# ProProject_007aLS_2024-05-12.net
KiCad netlist of a schematic drawn in EasyEDA Pro
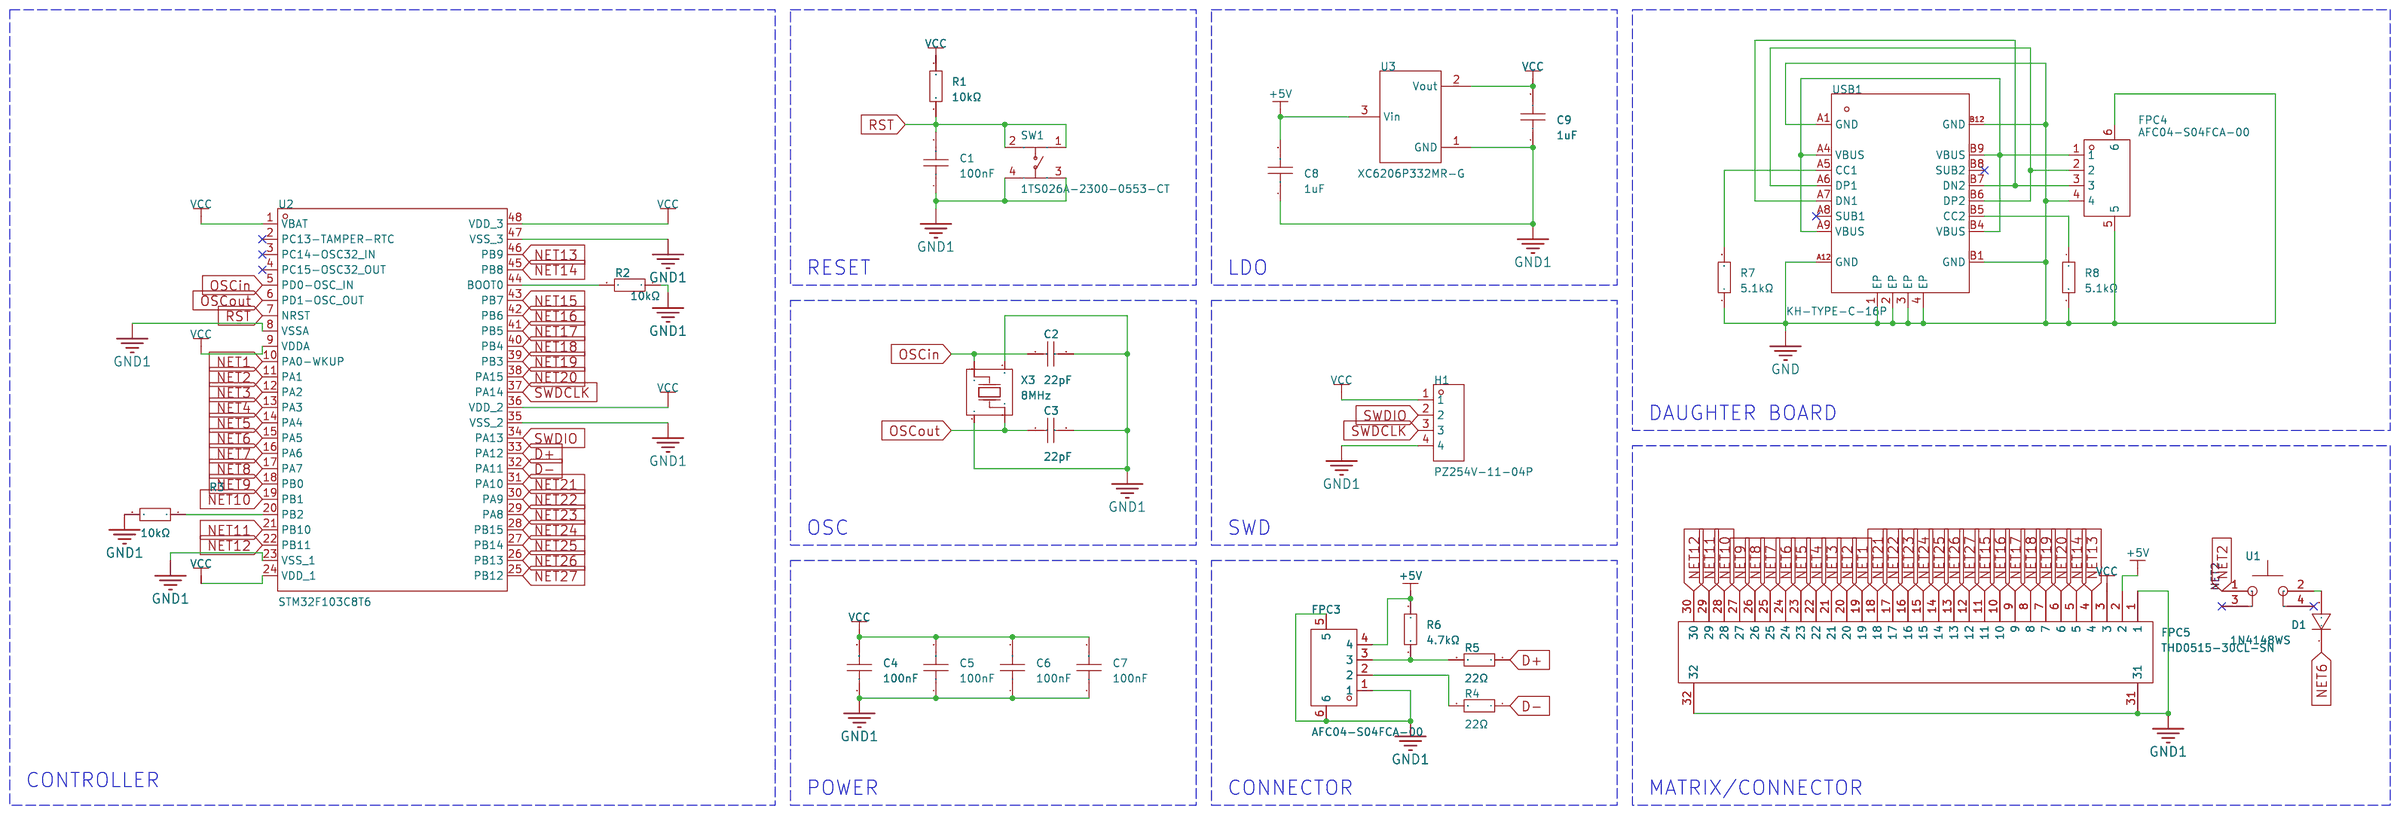
[diagram p0: schematic sheet]

(export (version "E")
  (design (tool "Eeschema 10.0.6"))
  (components
    (comp (ref "C1")
      (value "100nF")
      (footprint "easyedapro:C0603")
      (description "容值:100nF;精度:±10%;额定电压:50V;材质(温度系数):X7R;")
      (fields
        (field (name "Manufacturer Part") "CC0603KRX7R9BB104")
        (field (name "Manufacturer") "YAGEO(国巨)")
      )
      (libsource (lib "easyedapro") (part "CC0603KRX7R9BB104"))
    )
    (comp (ref "C2")
      (value "22pF")
      (footprint "easyedapro:C0603")
      (description "容值:22pF;精度:±5%;额定电压:50V;材质(温度系数):C0G;")
      (fields
        (field (name "Manufacturer Part") "CL10C220JB8NNNC")
        (field (name "Manufacturer") "SAMSUNG(三星)")
      )
      (libsource (lib "easyedapro") (part "CL10C220JB8NNNC"))
    )
    (comp (ref "C3")
      (value "22pF")
      (footprint "easyedapro:C0603")
      (description "容值:22pF;精度:±5%;额定电压:50V;材质(温度系数):C0G;")
      (fields
        (field (name "Manufacturer Part") "CL10C220JB8NNNC")
        (field (name "Manufacturer") "SAMSUNG(三星)")
      )
      (libsource (lib "easyedapro") (part "CL10C220JB8NNNC"))
    )
    (comp (ref "C4")
      (value "100nF")
      (footprint "easyedapro:C0603")
      (description "容值:100nF;精度:±10%;额定电压:50V;材质(温度系数):X7R;")
      (fields
        (field (name "Manufacturer Part") "CC0603KRX7R9BB104")
        (field (name "Manufacturer") "YAGEO(国巨)")
      )
      (libsource (lib "easyedapro") (part "CC0603KRX7R9BB104"))
    )
    (comp (ref "C5")
      (value "100nF")
      (footprint "easyedapro:C0603")
      (description "容值:100nF;精度:±10%;额定电压:50V;材质(温度系数):X7R;")
      (fields
        (field (name "Manufacturer Part") "CC0603KRX7R9BB104")
        (field (name "Manufacturer") "YAGEO(国巨)")
      )
      (libsource (lib "easyedapro") (part "CC0603KRX7R9BB104"))
    )
    (comp (ref "C6")
      (value "100nF")
      (footprint "easyedapro:C0603")
      (description "容值:100nF;精度:±10%;额定电压:50V;材质(温度系数):X7R;")
      (fields
        (field (name "Manufacturer Part") "CC0603KRX7R9BB104")
        (field (name "Manufacturer") "YAGEO(国巨)")
      )
      (libsource (lib "easyedapro") (part "CC0603KRX7R9BB104"))
    )
    (comp (ref "C7")
      (value "100nF")
      (footprint "easyedapro:C0603")
      (description "容值:100nF;精度:±10%;额定电压:50V;材质(温度系数):X7R;")
      (fields
        (field (name "Manufacturer Part") "CC0603KRX7R9BB104")
        (field (name "Manufacturer") "YAGEO(国巨)")
      )
      (libsource (lib "easyedapro") (part "CC0603KRX7R9BB104"))
    )
    (comp (ref "C8")
      (value "1uF")
      (footprint "easyedapro:C0603")
      (description "容值:1uF;精度:±10%;额定电压:50V;材质(温度系数):X5R;")
      (fields
        (field (name "Manufacturer Part") "CL10A105KB8NNNC")
        (field (name "Manufacturer") "SAMSUNG(三星)")
      )
      (libsource (lib "easyedapro") (part "CL10A105KB8NNNC"))
    )
    (comp (ref "C9")
      (value "1uF")
      (footprint "easyedapro:C0603")
      (description "容值:1uF;精度:±10%;额定电压:50V;材质(温度系数):X5R;")
      (fields
        (field (name "Manufacturer Part") "CL10A105KB8NNNC")
        (field (name "Manufacturer") "SAMSUNG(三星)")
      )
      (libsource (lib "easyedapro") (part "CL10A105KB8NNNC"))
    )
    (comp (ref "D1")
      (value "1N4148WS")
      (footprint "easyedapro:SOD-323_L1.8-W1.3-LS2.5-RD")
      (description "二极管配置:独立式;正向压降(Vf):1.25V@150mA;直流反向耐压(Vr):100V;平均整流电流(Io):150mA;功率:200mW;反向恢复时间(trr):4ns;")
      (fields (field (name "Manufacturer") "CJ(江苏长电/长晶)"))
      (libsource (lib "easyedapro") (part "1N4148WS T4"))
    )
    (comp (ref "FPC3")
      (value "AFC04-S04FCA-00")
      (footprint "easyedapro:FPC-SMD_AFC04-S04FCA-00")
      (description "锁定特性:抽屉式;触点类型:下接;触点数量:4P;间距:0.5mm;安装类型:卧贴;工作温度范围:-25°C~+85°C;")
      (fields (field (name "Manufacturer") "JS(钜硕电子)"))
      (libsource (lib "easyedapro") (part "AFC04-S04FCA-00"))
    )
    (comp (ref "FPC4")
      (value "AFC04-S04FCA-00")
      (footprint "easyedapro:FPC-SMD_AFC04-S04FCA-00")
      (description "锁定特性:抽屉式;触点类型:下接;触点数量:4P;间距:0.5mm;安装类型:卧贴;工作温度范围:-25°C~+85°C;")
      (fields (field (name "Manufacturer") "JS(钜硕电子)"))
      (libsource (lib "easyedapro") (part "AFC04-S04FCA-00"))
    )
    (comp (ref "FPC5")
      (value "THD0515-30CL-SN")
      (footprint "easyedapro:FFC-SMD_30P-P0.50_THD0515-30CL-SN")
      (description "锁定特性:翻盖式;触点类型:下接;触点数量:30P;间距:0.5mm;安装类型:卧贴;")
      (fields (field (name "Manufacturer") "THD(台华达)"))
      (libsource (lib "easyedapro") (part "THD0515-30CL-SN"))
    )
    (comp (ref "H1")
      (value "PZ254V-11-04P")
      (footprint "easyedapro:HDR-TH_4P-P2.54-V-M")
      (fields (field (name "Manufacturer") "XFCN(兴飞)"))
      (libsource (lib "easyedapro") (part "PZ254V-11-04P_C2691448"))
    )
    (comp (ref "R1")
      (value "10kΩ")
      (footprint "easyedapro:R0603")
      (description "电阻类型:厚膜电阻;阻值:10kΩ;精度:±1%;功率:100mW;最大工作电压:75V;温度系数:±100ppm/°C;")
      (fields
        (field (name "Manufacturer Part") "0603WAF1002T5E")
        (field (name "Manufacturer") "UNI-ROYAL(厚声)")
      )
      (libsource (lib "easyedapro") (part "0603WAF1002T5E"))
    )
    (comp (ref "R2")
      (value "10kΩ")
      (footprint "easyedapro:R0603")
      (description "电阻类型:厚膜电阻;阻值:10kΩ;精度:±1%;功率:100mW;最大工作电压:75V;温度系数:±100ppm/°C;")
      (fields
        (field (name "Manufacturer Part") "0603WAF1002T5E")
        (field (name "Manufacturer") "UNI-ROYAL(厚声)")
      )
      (libsource (lib "easyedapro") (part "0603WAF1002T5E"))
    )
    (comp (ref "R3")
      (value "10kΩ")
      (footprint "easyedapro:R0603")
      (description "电阻类型:厚膜电阻;阻值:10kΩ;精度:±1%;功率:100mW;最大工作电压:75V;温度系数:±100ppm/°C;")
      (fields
        (field (name "Manufacturer Part") "0603WAF1002T5E")
        (field (name "Manufacturer") "UNI-ROYAL(厚声)")
      )
      (libsource (lib "easyedapro") (part "0603WAF1002T5E"))
    )
    (comp (ref "R4")
      (value "22Ω")
      (footprint "easyedapro:R0603")
      (description "电阻类型:厚膜电阻;阻值:22Ω;精度:±1%;功率:100mW;最大工作电压:75V;温度系数:±100ppm/°C;")
      (fields
        (field (name "Manufacturer Part") "0603WAF220JT5E")
        (field (name "Manufacturer") "UNI-ROYAL(厚声)")
      )
      (libsource (lib "easyedapro") (part "0603WAF220JT5E"))
    )
    (comp (ref "R5")
      (value "22Ω")
      (footprint "easyedapro:R0603")
      (description "电阻类型:厚膜电阻;阻值:22Ω;精度:±1%;功率:100mW;最大工作电压:75V;温度系数:±100ppm/°C;")
      (fields
        (field (name "Manufacturer Part") "0603WAF220JT5E")
        (field (name "Manufacturer") "UNI-ROYAL(厚声)")
      )
      (libsource (lib "easyedapro") (part "0603WAF220JT5E"))
    )
    (comp (ref "R6")
      (value "4.7kΩ")
      (footprint "easyedapro:R0603")
      (description "电阻类型:厚膜电阻;阻值:4.7kΩ;精度:±1%;功率:100mW;最大工作电压:75V;温度系数:±100ppm/°C;")
      (fields
        (field (name "Manufacturer Part") "0603WAF4701T5E")
        (field (name "Manufacturer") "UNI-ROYAL(厚声)")
      )
      (libsource (lib "easyedapro") (part "0603WAF4701T5E"))
    )
    (comp (ref "R7")
      (value "5.1kΩ")
      (footprint "easyedapro:R0603")
      (description "电阻类型:厚膜电阻;阻值:5.1kΩ;精度:±1%;功率:100mW;最大工作电压:75V;温度系数:±100ppm/°C;")
      (fields
        (field (name "Manufacturer Part") "0603WAF5101T5E")
        (field (name "Manufacturer") "UNI-ROYAL(厚声)")
      )
      (libsource (lib "easyedapro") (part "0603WAF5101T5E"))
    )
    (comp (ref "R8")
      (value "5.1kΩ")
      (footprint "easyedapro:R0603")
      (description "电阻类型:厚膜电阻;阻值:5.1kΩ;精度:±1%;功率:100mW;最大工作电压:75V;温度系数:±100ppm/°C;")
      (fields
        (field (name "Manufacturer Part") "0603WAF5101T5E")
        (field (name "Manufacturer") "UNI-ROYAL(厚声)")
      )
      (libsource (lib "easyedapro") (part "0603WAF5101T5E"))
    )
    (comp (ref "SW1")
      (value "1TS026A-2300-0553-CT")
      (footprint "easyedapro:SW-SMD_4P-L2.6-W1.6-P0.75-LS3.0")
      (fields (field (name "Manufacturer") "HYP(鸿源精密)"))
      (libsource (lib "easyedapro") (part "1TS026A-2300-0553-CT"))
    )
    (comp (ref "U1")
      (value "~")
      (footprint "easyedapro:MXOnly-6.25U/7U-Hotswap-ReversedStabilizers")
      (libsource (lib "easyedapro") (part "MXOnly-6.25U/7U-Hotswap-ReversedStabilizers"))
    )
    (comp (ref "U2")
      (value "STM32F103C8T6")
      (footprint "easyedapro:LQFP-48_L7.0-W7.0-P0.50-LS9.0-BL")
      (description "CPU内核:CM3;程序存储容量:64KB;RAM总容量:20KB;GPIO端口数量:37;工作电压范围:2V~3.6V;CPU最大主频:72MHz;程序存储器类型:FLASH;")
      (fields (field (name "Manufacturer") "ST(意法半导体)"))
      (libsource (lib "easyedapro") (part "STM32F103C8T6"))
    )
    (comp (ref "U3")
      (value "XC6206P332MR-G")
      (footprint "easyedapro:SOT-23-3_L2.9-W1.6-P1.90-LS2.8-BR")
      (description "输出类型:固定;最大输入电压:6V;输出电压:3.3V;最大输出电流:200mA;电源纹波抑制比(PSRR):-;输出极性:正极;")
      (fields (field (name "Manufacturer") "TOREX(特瑞仕)"))
      (libsource (lib "easyedapro") (part "XC6206P332MR"))
    )
    (comp (ref "USB1")
      (value "KH-TYPE-C-16P")
      (footprint "easyedapro:USB-C-SMD_KH-TYPE-C-16P")
      (description "连接器类型:Type-C;标准:-;公母:母;端口数量:1;触点数量:16P;安装方式:卧贴;额定电流 - 电源:3A;工作温度范围:-40°C~+85°C;")
      (fields (field (name "Manufacturer") "kinghelm(金航标)"))
      (libsource (lib "easyedapro") (part "KH-TYPE-C-16P"))
    )
    (comp (ref "X3")
      (value "8MHz")
      (footprint "easyedapro:OSC-SMD_4P-L3.2-W2.5-BL")
      (description "晶振类型:贴片晶振;频率:8MHz;常温频差:±10ppm;外接负载电容:10pF;频率稳定度(全温):±15ppm;")
      (fields (field (name "Manufacturer Part") "TAXM8M4RDBCCT2T") (field (name "Manufacturer") "YJX(雅晶鑫)"))
      (libsource (lib "easyedapro") (part "TAXM8M4RDBCCT2T"))
    )
  )
  (nets
    (net (code "1") (name "+5V") (class "Default")
      (node (ref "C8") (pin "2") (pinfunction "2_2") (pintype "unspecified"))
      (node (ref "FPC3") (pin "4") (pinfunction "4_4") (pintype "unspecified"))
      (node (ref "FPC5") (pin "2") (pinfunction "2_2") (pintype "unspecified"))
      (node (ref "R6") (pin "2") (pinfunction "2_2") (pintype "input"))
      (node (ref "U3") (pin "3") (pinfunction "Vin_3") (pintype "unspecified"))
    )
    (net (code "2") (name "D+") (class "Default")
      (node (ref "R5") (pin "1") (pinfunction "1_1") (pintype "input"))
      (node (ref "U2") (pin "33") (pinfunction "PA12_33") (pintype "unspecified"))
    )
    (net (code "3") (name "D-") (class "Default")
      (node (ref "R4") (pin "1") (pinfunction "1_1") (pintype "input"))
      (node (ref "U2") (pin "32") (pinfunction "PA11_32") (pintype "unspecified"))
    )
    (net (code "4") (name "GND") (class "Default")
      (node (ref "FPC4") (pin "4") (pinfunction "4_4") (pintype "unspecified"))
      (node (ref "FPC4") (pin "5") (pinfunction "5_5") (pintype "unspecified"))
      (node (ref "FPC4") (pin "6") (pinfunction "6_6") (pintype "unspecified"))
      (node (ref "R7") (pin "1") (pinfunction "1_1") (pintype "input"))
      (node (ref "R8") (pin "2") (pinfunction "2_2") (pintype "input"))
      (node (ref "USB1") (pin "1") (pinfunction "EP_1") (pintype "unspecified"))
      (node (ref "USB1") (pin "2") (pinfunction "EP_2") (pintype "unspecified"))
      (node (ref "USB1") (pin "3") (pinfunction "EP_3") (pintype "unspecified"))
      (node (ref "USB1") (pin "4") (pinfunction "EP_4") (pintype "unspecified"))
      (node (ref "USB1") (pin "A1") (pinfunction "GND_A1") (pintype "unspecified"))
      (node (ref "USB1") (pin "A12") (pinfunction "GND_A12") (pintype "unspecified"))
      (node (ref "USB1") (pin "B1") (pinfunction "GND_B1") (pintype "unspecified"))
      (node (ref "USB1") (pin "B12") (pinfunction "GND_B12") (pintype "unspecified"))
    )
    (net (code "5") (name "GND1") (class "Default")
      (node (ref "C1") (pin "1") (pinfunction "1_1") (pintype "unspecified"))
      (node (ref "C2") (pin "2") (pinfunction "2_2") (pintype "input"))
      (node (ref "C3") (pin "2") (pinfunction "2_2") (pintype "input"))
      (node (ref "C4") (pin "1") (pinfunction "1_1") (pintype "unspecified"))
      (node (ref "C5") (pin "1") (pinfunction "1_1") (pintype "unspecified"))
      (node (ref "C6") (pin "1") (pinfunction "1_1") (pintype "unspecified"))
      (node (ref "C7") (pin "1") (pinfunction "1_1") (pintype "unspecified"))
      (node (ref "C8") (pin "1") (pinfunction "1_1") (pintype "unspecified"))
      (node (ref "C9") (pin "1") (pinfunction "1_1") (pintype "unspecified"))
      (node (ref "FPC3") (pin "1") (pinfunction "1_1") (pintype "unspecified"))
      (node (ref "FPC3") (pin "5") (pinfunction "5_5") (pintype "unspecified"))
      (node (ref "FPC3") (pin "6") (pinfunction "6_6") (pintype "unspecified"))
      (node (ref "FPC5") (pin "1") (pinfunction "1_1") (pintype "unspecified"))
      (node (ref "FPC5") (pin "31") (pinfunction "31_31") (pintype "unspecified"))
      (node (ref "FPC5") (pin "32") (pinfunction "32_32") (pintype "unspecified"))
      (node (ref "H1") (pin "4") (pinfunction "4_4") (pintype "unspecified"))
      (node (ref "R2") (pin "1") (pinfunction "1_1") (pintype "input"))
      (node (ref "R3") (pin "2") (pinfunction "2_2") (pintype "input"))
      (node (ref "SW1") (pin "3") (pinfunction "3_3") (pintype "input"))
      (node (ref "SW1") (pin "4") (pinfunction "4_4") (pintype "input"))
      (node (ref "U2") (pin "23") (pinfunction "VSS_1_23") (pintype "unspecified"))
      (node (ref "U2") (pin "35") (pinfunction "VSS_2_35") (pintype "unspecified"))
      (node (ref "U2") (pin "47") (pinfunction "VSS_3_47") (pintype "unspecified"))
      (node (ref "U2") (pin "8") (pinfunction "VSSA_8") (pintype "unspecified"))
      (node (ref "U3") (pin "1") (pinfunction "GND_1") (pintype "unspecified"))
      (node (ref "X3") (pin "2") (pinfunction "2_2") (pintype "input"))
      (node (ref "X3") (pin "4") (pinfunction "4_4") (pintype "input"))
    )
    (net (code "6") (name "NET1") (class "Default")
      (node (ref "FPC5") (pin "19") (pinfunction "19_19") (pintype "unspecified"))
      (node (ref "U2") (pin "10") (pinfunction "PA0-WKUP_10") (pintype "unspecified"))
    )
    (net (code "7") (name "NET2") (class "Default")
      (node (ref "FPC5") (pin "20") (pinfunction "20_20") (pintype "unspecified"))
      (node (ref "U1") (pin "1") (pinfunction "1_1") (pintype "input"))
      (node (ref "U2") (pin "11") (pinfunction "PA1_11") (pintype "unspecified"))
    )
    (net (code "8") (name "NET3") (class "Default")
      (node (ref "FPC5") (pin "21") (pinfunction "21_21") (pintype "unspecified"))
      (node (ref "U2") (pin "12") (pinfunction "PA2_12") (pintype "unspecified"))
    )
    (net (code "9") (name "NET4") (class "Default")
      (node (ref "FPC5") (pin "22") (pinfunction "22_22") (pintype "unspecified"))
      (node (ref "U2") (pin "13") (pinfunction "PA3_13") (pintype "unspecified"))
    )
    (net (code "10") (name "NET5") (class "Default")
      (node (ref "FPC5") (pin "23") (pinfunction "23_23") (pintype "unspecified"))
      (node (ref "U2") (pin "14") (pinfunction "PA4_14") (pintype "unspecified"))
    )
    (net (code "11") (name "NET6") (class "Default")
      (node (ref "D1") (pin "1") (pinfunction "K_1") (pintype "unspecified"))
      (node (ref "FPC5") (pin "24") (pinfunction "24_24") (pintype "unspecified"))
      (node (ref "U2") (pin "15") (pinfunction "PA5_15") (pintype "unspecified"))
    )
    (net (code "12") (name "NET7") (class "Default")
      (node (ref "FPC5") (pin "25") (pinfunction "25_25") (pintype "unspecified"))
      (node (ref "U2") (pin "16") (pinfunction "PA6_16") (pintype "unspecified"))
    )
    (net (code "13") (name "NET8") (class "Default")
      (node (ref "FPC5") (pin "26") (pinfunction "26_26") (pintype "unspecified"))
      (node (ref "U2") (pin "17") (pinfunction "PA7_17") (pintype "unspecified"))
    )
    (net (code "14") (name "NET9") (class "Default")
      (node (ref "FPC5") (pin "27") (pinfunction "27_27") (pintype "unspecified"))
      (node (ref "U2") (pin "18") (pinfunction "PB0_18") (pintype "unspecified"))
    )
    (net (code "15") (name "NET10") (class "Default")
      (node (ref "FPC5") (pin "28") (pinfunction "28_28") (pintype "unspecified"))
      (node (ref "U2") (pin "19") (pinfunction "PB1_19") (pintype "unspecified"))
    )
    (net (code "16") (name "NET11") (class "Default")
      (node (ref "FPC5") (pin "29") (pinfunction "29_29") (pintype "unspecified"))
      (node (ref "U2") (pin "21") (pinfunction "PB10_21") (pintype "unspecified"))
    )
    (net (code "17") (name "NET12") (class "Default")
      (node (ref "FPC5") (pin "30") (pinfunction "30_30") (pintype "unspecified"))
      (node (ref "U2") (pin "22") (pinfunction "PB11_22") (pintype "unspecified"))
    )
    (net (code "18") (name "NET13") (class "Default")
      (node (ref "FPC5") (pin "4") (pinfunction "4_4") (pintype "unspecified"))
      (node (ref "U2") (pin "46") (pinfunction "PB9_46") (pintype "unspecified"))
    )
    (net (code "19") (name "NET14") (class "Default")
      (node (ref "FPC5") (pin "5") (pinfunction "5_5") (pintype "unspecified"))
      (node (ref "U2") (pin "45") (pinfunction "PB8_45") (pintype "unspecified"))
    )
    (net (code "20") (name "NET15") (class "Default")
      (node (ref "FPC5") (pin "11") (pinfunction "11_11") (pintype "unspecified"))
      (node (ref "U2") (pin "43") (pinfunction "PB7_43") (pintype "unspecified"))
    )
    (net (code "21") (name "NET16") (class "Default")
      (node (ref "FPC5") (pin "10") (pinfunction "10_10") (pintype "unspecified"))
      (node (ref "U2") (pin "42") (pinfunction "PB6_42") (pintype "unspecified"))
    )
    (net (code "22") (name "NET17") (class "Default")
      (node (ref "FPC5") (pin "9") (pinfunction "9_9") (pintype "unspecified"))
      (node (ref "U2") (pin "41") (pinfunction "PB5_41") (pintype "unspecified"))
    )
    (net (code "23") (name "NET18") (class "Default")
      (node (ref "FPC5") (pin "8") (pinfunction "8_8") (pintype "unspecified"))
      (node (ref "U2") (pin "40") (pinfunction "PB4_40") (pintype "unspecified"))
    )
    (net (code "24") (name "NET19") (class "Default")
      (node (ref "FPC5") (pin "7") (pinfunction "7_7") (pintype "unspecified"))
      (node (ref "U2") (pin "39") (pinfunction "PB3_39") (pintype "unspecified"))
    )
    (net (code "25") (name "NET20") (class "Default")
      (node (ref "FPC5") (pin "6") (pinfunction "6_6") (pintype "unspecified"))
      (node (ref "U2") (pin "38") (pinfunction "PA15_38") (pintype "unspecified"))
    )
    (net (code "26") (name "NET21") (class "Default")
      (node (ref "FPC5") (pin "18") (pinfunction "18_18") (pintype "unspecified"))
      (node (ref "U2") (pin "31") (pinfunction "PA10_31") (pintype "unspecified"))
    )
    (net (code "27") (name "NET22") (class "Default")
      (node (ref "FPC5") (pin "17") (pinfunction "17_17") (pintype "unspecified"))
      (node (ref "U2") (pin "30") (pinfunction "PA9_30") (pintype "unspecified"))
    )
    (net (code "28") (name "NET23") (class "Default")
      (node (ref "FPC5") (pin "16") (pinfunction "16_16") (pintype "unspecified"))
      (node (ref "U2") (pin "29") (pinfunction "PA8_29") (pintype "unspecified"))
    )
    (net (code "29") (name "NET24") (class "Default")
      (node (ref "FPC5") (pin "15") (pinfunction "15_15") (pintype "unspecified"))
      (node (ref "U2") (pin "28") (pinfunction "PB15_28") (pintype "unspecified"))
    )
    (net (code "30") (name "NET25") (class "Default")
      (node (ref "FPC5") (pin "14") (pinfunction "14_14") (pintype "unspecified"))
      (node (ref "U2") (pin "27") (pinfunction "PB14_27") (pintype "unspecified"))
    )
    (net (code "31") (name "NET26") (class "Default")
      (node (ref "FPC5") (pin "13") (pinfunction "13_13") (pintype "unspecified"))
      (node (ref "U2") (pin "26") (pinfunction "PB13_26") (pintype "unspecified"))
    )
    (net (code "32") (name "NET27") (class "Default")
      (node (ref "FPC5") (pin "12") (pinfunction "12_12") (pintype "unspecified"))
      (node (ref "U2") (pin "25") (pinfunction "PB12_25") (pintype "unspecified"))
    )
    (net (code "33") (name "Net-(D1-A)") (class "Default")
      (node (ref "D1") (pin "2") (pinfunction "A_2") (pintype "unspecified"))
      (node (ref "U1") (pin "2") (pinfunction "2_2") (pintype "input"))
    )
    (net (code "34") (name "Net-(FPC3-Pad2)") (class "Default")
      (node (ref "FPC3") (pin "2") (pinfunction "2_2") (pintype "unspecified"))
      (node (ref "R4") (pin "2") (pinfunction "2_2") (pintype "input"))
    )
    (net (code "35") (name "Net-(FPC3-Pad3)") (class "Default")
      (node (ref "FPC3") (pin "3") (pinfunction "3_3") (pintype "unspecified"))
      (node (ref "R5") (pin "2") (pinfunction "2_2") (pintype "input"))
      (node (ref "R6") (pin "1") (pinfunction "1_1") (pintype "input"))
    )
    (net (code "36") (name "Net-(FPC4-Pad1)") (class "Default")
      (node (ref "FPC4") (pin "1") (pinfunction "1_1") (pintype "unspecified"))
      (node (ref "USB1") (pin "A4") (pinfunction "VBUS_A4") (pintype "unspecified"))
      (node (ref "USB1") (pin "A9") (pinfunction "VBUS_A9") (pintype "unspecified"))
      (node (ref "USB1") (pin "B4") (pinfunction "VBUS_B4") (pintype "unspecified"))
      (node (ref "USB1") (pin "B9") (pinfunction "VBUS_B9") (pintype "unspecified"))
    )
    (net (code "37") (name "Net-(U2-BOOT0)") (class "Default")
      (node (ref "R2") (pin "2") (pinfunction "2_2") (pintype "input"))
      (node (ref "U2") (pin "44") (pinfunction "BOOT0_44") (pintype "unspecified"))
    )
    (net (code "38") (name "Net-(U2-PB2)") (class "Default")
      (node (ref "R3") (pin "1") (pinfunction "1_1") (pintype "input"))
      (node (ref "U2") (pin "20") (pinfunction "PB2_20") (pintype "unspecified"))
    )
    (net (code "39") (name "Net-(USB1-CC1)") (class "Default")
      (node (ref "R7") (pin "2") (pinfunction "2_2") (pintype "input"))
      (node (ref "USB1") (pin "A5") (pinfunction "CC1_A5") (pintype "unspecified"))
    )
    (net (code "40") (name "Net-(USB1-CC2)") (class "Default")
      (node (ref "R8") (pin "1") (pinfunction "1_1") (pintype "input"))
      (node (ref "USB1") (pin "B5") (pinfunction "CC2_B5") (pintype "unspecified"))
    )
    (net (code "41") (name "Net-(USB1-DN1)") (class "Default")
      (node (ref "FPC4") (pin "3") (pinfunction "3_3") (pintype "unspecified"))
      (node (ref "USB1") (pin "A7") (pinfunction "DN1_A7") (pintype "unspecified"))
      (node (ref "USB1") (pin "B7") (pinfunction "DN2_B7") (pintype "unspecified"))
    )
    (net (code "42") (name "Net-(USB1-DP1)") (class "Default")
      (node (ref "FPC4") (pin "2") (pinfunction "2_2") (pintype "unspecified"))
      (node (ref "USB1") (pin "A6") (pinfunction "DP1_A6") (pintype "unspecified"))
      (node (ref "USB1") (pin "B6") (pinfunction "DP2_B6") (pintype "unspecified"))
    )
    (net (code "43") (name "OSCin") (class "Default")
      (node (ref "C2") (pin "1") (pinfunction "1_1") (pintype "input"))
      (node (ref "U2") (pin "5") (pinfunction "PD0-OSC_IN_5") (pintype "unspecified"))
      (node (ref "X3") (pin "3") (pinfunction "3_3") (pintype "input"))
    )
    (net (code "44") (name "OSCout") (class "Default")
      (node (ref "C3") (pin "1") (pinfunction "1_1") (pintype "input"))
      (node (ref "U2") (pin "6") (pinfunction "PD1-OSC_OUT_6") (pintype "unspecified"))
      (node (ref "X3") (pin "1") (pinfunction "1_1") (pintype "input"))
    )
    (net (code "45") (name "RST") (class "Default")
      (node (ref "C1") (pin "2") (pinfunction "2_2") (pintype "unspecified"))
      (node (ref "R1") (pin "1") (pinfunction "1_1") (pintype "input"))
      (node (ref "SW1") (pin "1") (pinfunction "1_1") (pintype "input"))
      (node (ref "SW1") (pin "2") (pinfunction "2_2") (pintype "input"))
      (node (ref "U2") (pin "7") (pinfunction "NRST_7") (pintype "unspecified"))
    )
    (net (code "46") (name "SWDCLK") (class "Default")
      (node (ref "H1") (pin "3") (pinfunction "3_3") (pintype "unspecified"))
      (node (ref "U2") (pin "37") (pinfunction "PA14_37") (pintype "unspecified"))
    )
    (net (code "47") (name "SWDIO") (class "Default")
      (node (ref "H1") (pin "2") (pinfunction "2_2") (pintype "unspecified"))
      (node (ref "U2") (pin "34") (pinfunction "PA13_34") (pintype "unspecified"))
    )
    (net (code "48") (name "VCC") (class "Default")
      (node (ref "C4") (pin "2") (pinfunction "2_2") (pintype "unspecified"))
      (node (ref "C5") (pin "2") (pinfunction "2_2") (pintype "unspecified"))
      (node (ref "C6") (pin "2") (pinfunction "2_2") (pintype "unspecified"))
      (node (ref "C7") (pin "2") (pinfunction "2_2") (pintype "unspecified"))
      (node (ref "C9") (pin "2") (pinfunction "2_2") (pintype "unspecified"))
      (node (ref "FPC5") (pin "3") (pinfunction "3_3") (pintype "unspecified"))
      (node (ref "H1") (pin "1") (pinfunction "1_1") (pintype "unspecified"))
      (node (ref "R1") (pin "2") (pinfunction "2_2") (pintype "input"))
      (node (ref "U2") (pin "1") (pinfunction "VBAT_1") (pintype "unspecified"))
      (node (ref "U2") (pin "24") (pinfunction "VDD_1_24") (pintype "unspecified"))
      (node (ref "U2") (pin "36") (pinfunction "VDD_2_36") (pintype "unspecified"))
      (node (ref "U2") (pin "48") (pinfunction "VDD_3_48") (pintype "unspecified"))
      (node (ref "U2") (pin "9") (pinfunction "VDDA_9") (pintype "unspecified"))
      (node (ref "U3") (pin "2") (pinfunction "Vout_2") (pintype "unspecified"))
    )
    (net (code "49") (name "unconnected-(U1-Pad3)") (class "Default")
      (node (ref "U1") (pin "3") (pinfunction "3_3") (pintype "input+no_connect"))
    )
    (net (code "50") (name "unconnected-(U1-Pad4)") (class "Default")
      (node (ref "U1") (pin "4") (pinfunction "4_4") (pintype "input+no_connect"))
    )
    (net (code "51") (name "unconnected-(U2-PC13-TAMPER-RTC-Pad2)") (class "Default")
      (node (ref "U2") (pin "2") (pinfunction "PC13-TAMPER-RTC_2") (pintype "unspecified+no_connect"))
    )
    (net (code "52") (name "unconnected-(U2-PC14-OSC32_IN-Pad3)") (class "Default")
      (node (ref "U2") (pin "3") (pinfunction "PC14-OSC32_IN_3") (pintype "unspecified+no_connect"))
    )
    (net (code "53") (name "unconnected-(U2-PC15-OSC32_OUT-Pad4)") (class "Default")
      (node (ref "U2") (pin "4") (pinfunction "PC15-OSC32_OUT_4") (pintype "unspecified+no_connect"))
    )
    (net (code "54") (name "unconnected-(USB1-SUB1-PadA8)") (class "Default")
      (node (ref "USB1") (pin "A8") (pinfunction "SUB1_A8") (pintype "unspecified+no_connect"))
    )
    (net (code "55") (name "unconnected-(USB1-SUB2-PadB8)") (class "Default")
      (node (ref "USB1") (pin "B8") (pinfunction "SUB2_B8") (pintype "unspecified+no_connect"))
    )
  )
)
